# MCU.net
KiCad netlist of a schematic drawn in Altium Designer
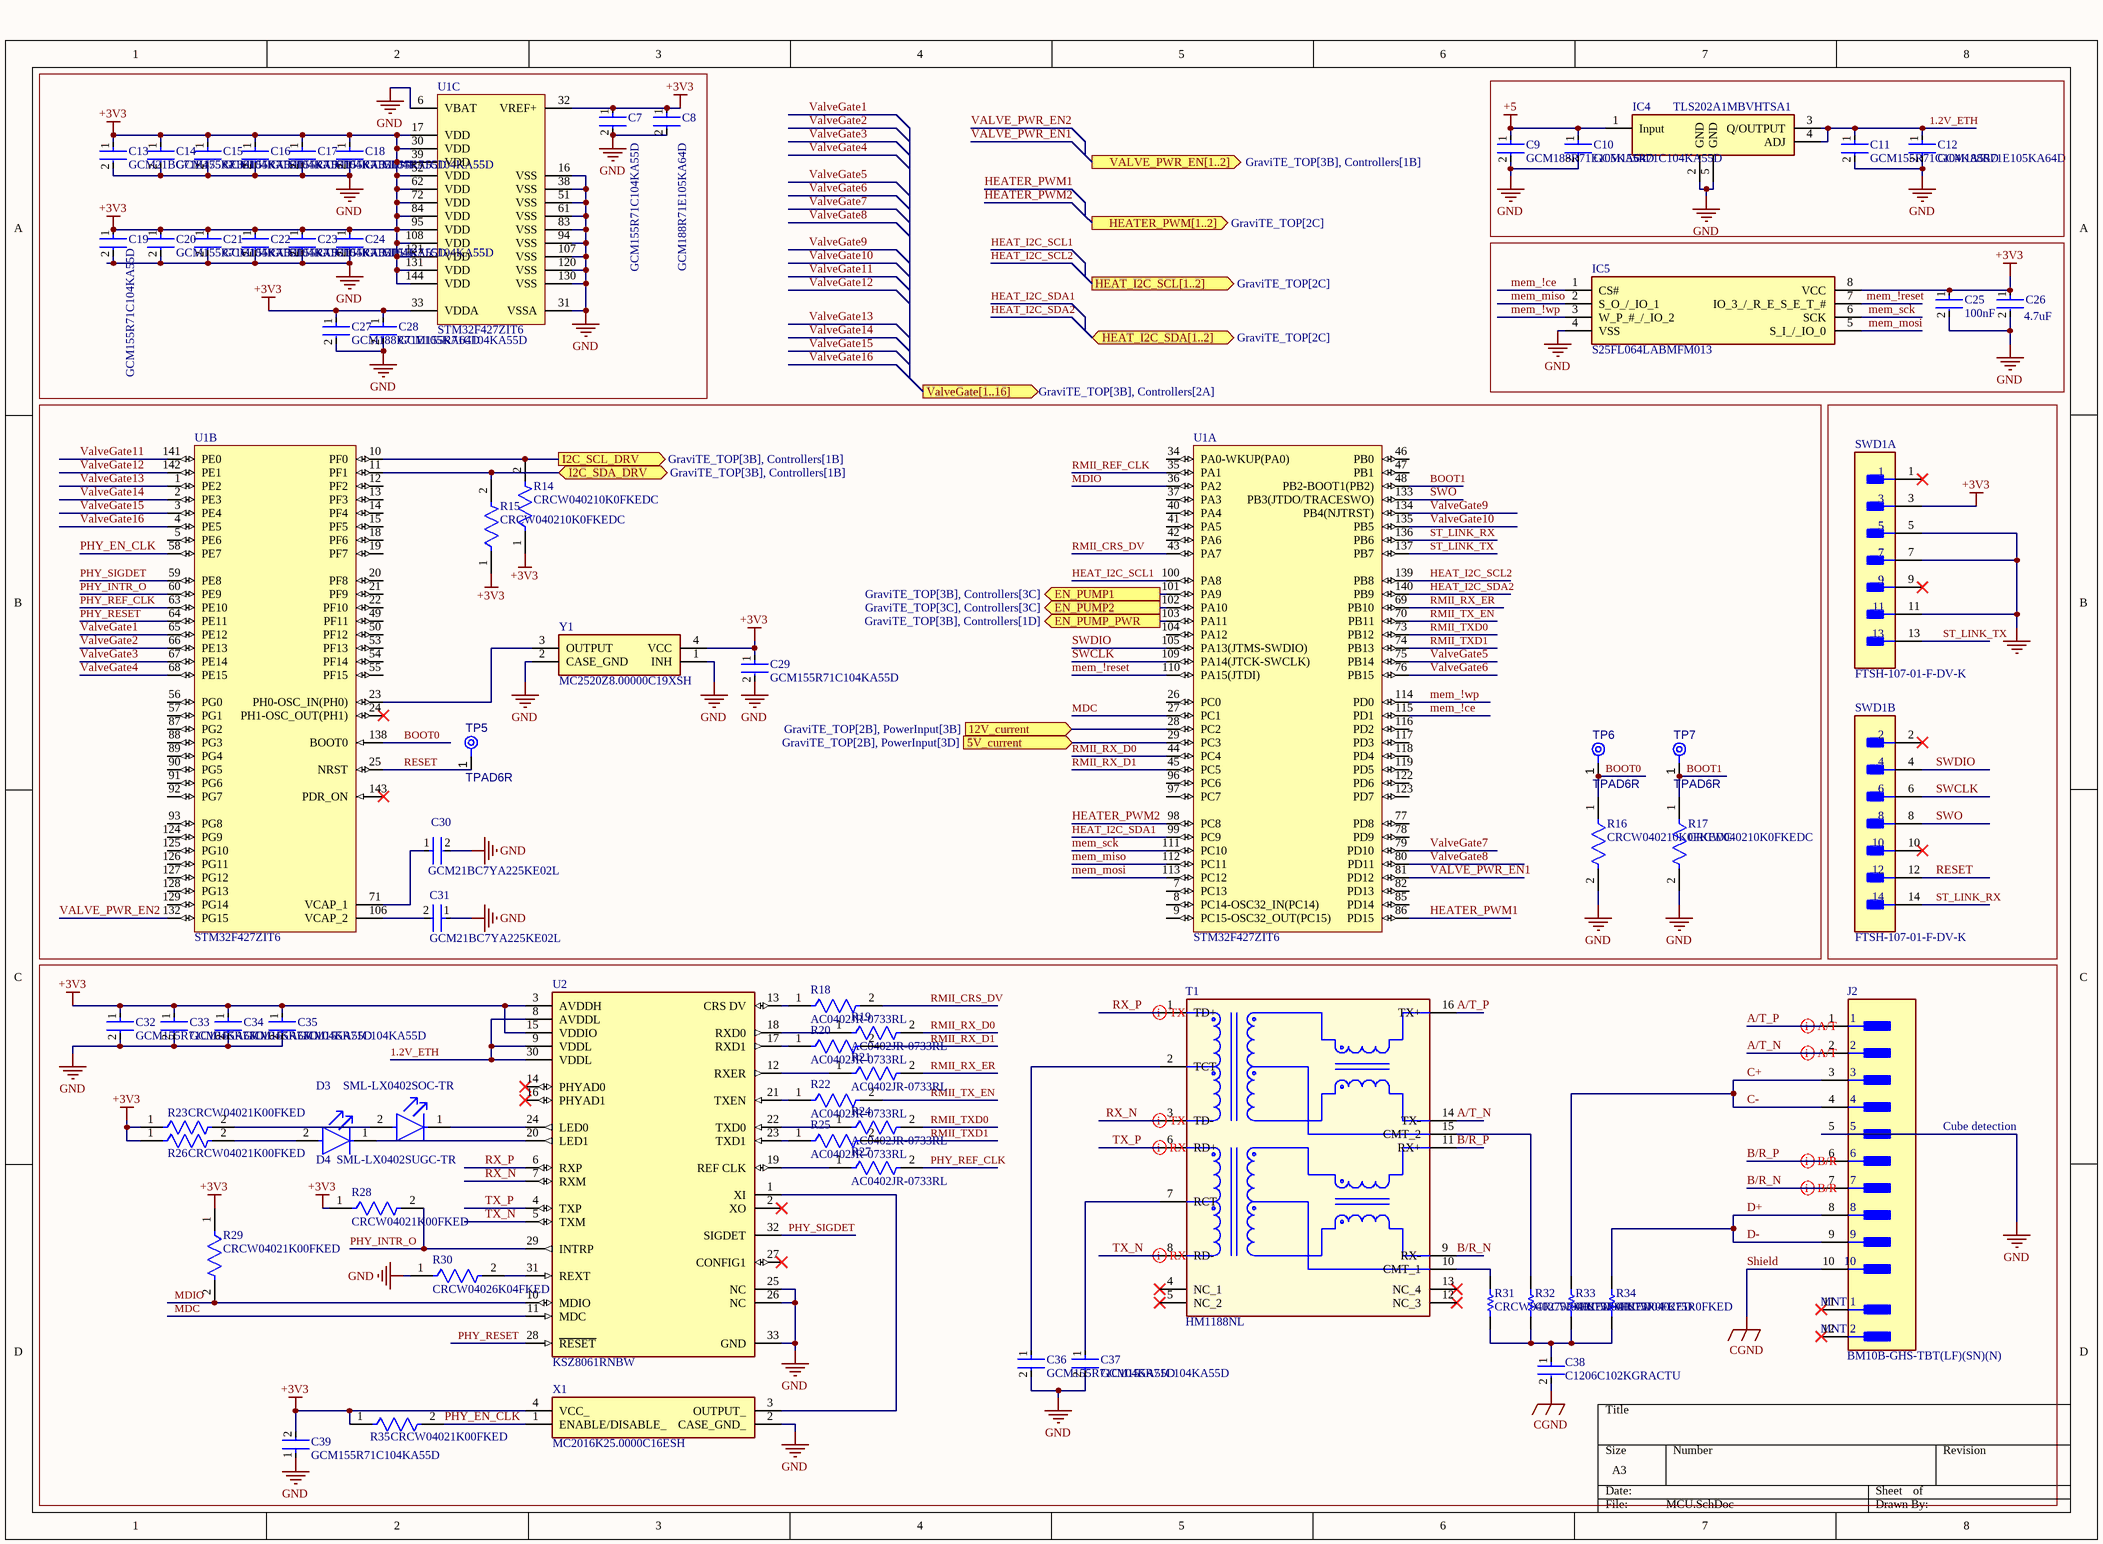
[diagram p0: MCU.SchDoc]

(export (version "E")
  (design (tool "Eeschema 10.0.6"))
  (components
    (comp (ref "C7")
      (value "GCM155R71C104KA55D")
      (footprint "FP-GCM155-0_05-IPC_C")
      (description "Ceramic Capacitor for Automotive 100nF ±10% 16VDC X7R 0402 Paper T/R")
      (fields (field (name "VOLTAGE") "16V") (field (name "TOLERANCE") "10%"))
      (libsource (lib "Altium Content Vault") (part "02cd4be3c70576c341d710602a673aa"))
    )
    (comp (ref "C8")
      (value "GCM188R71E105KA64D")
      (footprint "FP-GCM188-0_1-MFG")
      (fields (field (name "TOLERANCE") "10%") (field (name "VOLTAGE") "25V"))
      (libsource (lib "Altium Content Vault") (part "02cd4be3c70576c341d710602a673aa"))
    )
    (comp (ref "C9")
      (value "GCM188R71E105KA64D")
      (footprint "FP-GCM188-0_1-MFG")
      (fields (field (name "TOLERANCE") "10%") (field (name "VOLTAGE") "25V"))
      (libsource (lib "Altium Content Vault") (part "02cd4be3c70576c341d710602a673aa"))
    )
    (comp (ref "C10")
      (value "GCM155R71C104KA55D")
      (footprint "FP-GCM155-0_05-IPC_C")
      (description "Ceramic Capacitor for Automotive 100nF ±10% 16VDC X7R 0402 Paper T/R")
      (fields (field (name "VOLTAGE") "16V") (field (name "TOLERANCE") "10%"))
      (libsource (lib "Altium Content Vault") (part "02cd4be3c70576c341d710602a673aa"))
    )
    (comp (ref "C11")
      (value "GCM155R71C104KA55D")
      (footprint "FP-GCM155-0_05-IPC_C")
      (description "Ceramic Capacitor for Automotive 100nF ±10% 16VDC X7R 0402 Paper T/R")
      (fields (field (name "VOLTAGE") "16V") (field (name "TOLERANCE") "10%"))
      (libsource (lib "Altium Content Vault") (part "02cd4be3c70576c341d710602a673aa"))
    )
    (comp (ref "C12")
      (value "GCM188R71E105KA64D")
      (footprint "FP-GCM188-0_1-MFG")
      (fields (field (name "TOLERANCE") "10%") (field (name "VOLTAGE") "25V"))
      (libsource (lib "Altium Content Vault") (part "02cd4be3c70576c341d710602a673aa"))
    )
    (comp (ref "C13")
      (value "GCM21BC71E475KE36L")
      (footprint "FP-GCM21B-0_2-e0_2_0_7-IPC_C")
      (description "Ceramic Capacitor for Automotive 4.7uF ±10% 25VDC X7S 0805 Embossed T/R")
      (fields (field (name "TOLERANCE") "10%"))
      (libsource (lib "Altium Content Vault") (part "11868f565c42a9108669ba33697ecf6"))
    )
    (comp (ref "C14")
      (value "GCM155R71C104KA55D")
      (footprint "FP-GCM155-0_05-IPC_C")
      (description "Ceramic Capacitor for Automotive 100nF ±10% 16VDC X7R 0402 Paper T/R")
      (fields (field (name "VOLTAGE") "16V") (field (name "TOLERANCE") "10%"))
      (libsource (lib "Altium Content Vault") (part "02cd4be3c70576c341d710602a673aa"))
    )
    (comp (ref "C15")
      (value "GCM155R71C104KA55D")
      (footprint "FP-GCM155-0_05-IPC_C")
      (description "Ceramic Capacitor for Automotive 100nF ±10% 16VDC X7R 0402 Paper T/R")
      (fields (field (name "VOLTAGE") "16V") (field (name "TOLERANCE") "10%"))
      (libsource (lib "Altium Content Vault") (part "02cd4be3c70576c341d710602a673aa"))
    )
    (comp (ref "C16")
      (value "GCM155R71C104KA55D")
      (footprint "FP-GCM155-0_05-IPC_C")
      (description "Ceramic Capacitor for Automotive 100nF ±10% 16VDC X7R 0402 Paper T/R")
      (fields (field (name "VOLTAGE") "16V") (field (name "TOLERANCE") "10%"))
      (libsource (lib "Altium Content Vault") (part "02cd4be3c70576c341d710602a673aa"))
    )
    (comp (ref "C17")
      (value "GCM155R71C104KA55D")
      (footprint "FP-GCM155-0_05-IPC_C")
      (description "Ceramic Capacitor for Automotive 100nF ±10% 16VDC X7R 0402 Paper T/R")
      (fields (field (name "VOLTAGE") "16V") (field (name "TOLERANCE") "10%"))
      (libsource (lib "Altium Content Vault") (part "02cd4be3c70576c341d710602a673aa"))
    )
    (comp (ref "C18")
      (value "GCM155R71C104KA55D")
      (footprint "FP-GCM155-0_05-IPC_C")
      (description "Ceramic Capacitor for Automotive 100nF ±10% 16VDC X7R 0402 Paper T/R")
      (fields (field (name "VOLTAGE") "16V") (field (name "TOLERANCE") "10%"))
      (libsource (lib "Altium Content Vault") (part "02cd4be3c70576c341d710602a673aa"))
    )
    (comp (ref "C19")
      (value "GCM155R71C104KA55D")
      (footprint "FP-GCM155-0_05-IPC_C")
      (description "Ceramic Capacitor for Automotive 100nF ±10% 16VDC X7R 0402 Paper T/R")
      (fields (field (name "VOLTAGE") "16V") (field (name "TOLERANCE") "10%"))
      (libsource (lib "Altium Content Vault") (part "02cd4be3c70576c341d710602a673aa"))
    )
    (comp (ref "C20")
      (value "GCM155R71C104KA55D")
      (footprint "FP-GCM155-0_05-IPC_C")
      (description "Ceramic Capacitor for Automotive 100nF ±10% 16VDC X7R 0402 Paper T/R")
      (fields (field (name "VOLTAGE") "16V") (field (name "TOLERANCE") "10%"))
      (libsource (lib "Altium Content Vault") (part "02cd4be3c70576c341d710602a673aa"))
    )
    (comp (ref "C21")
      (value "GCM155R71C104KA55D")
      (footprint "FP-GCM155-0_05-IPC_C")
      (description "Ceramic Capacitor for Automotive 100nF ±10% 16VDC X7R 0402 Paper T/R")
      (fields (field (name "VOLTAGE") "16V") (field (name "TOLERANCE") "10%"))
      (libsource (lib "Altium Content Vault") (part "02cd4be3c70576c341d710602a673aa"))
    )
    (comp (ref "C22")
      (value "GCM155R71C104KA55D")
      (footprint "FP-GCM155-0_05-IPC_C")
      (description "Ceramic Capacitor for Automotive 100nF ±10% 16VDC X7R 0402 Paper T/R")
      (fields (field (name "VOLTAGE") "16V") (field (name "TOLERANCE") "10%"))
      (libsource (lib "Altium Content Vault") (part "02cd4be3c70576c341d710602a673aa"))
    )
    (comp (ref "C23")
      (value "GCM155R71C104KA55D")
      (footprint "FP-GCM155-0_05-IPC_C")
      (description "Ceramic Capacitor for Automotive 100nF ±10% 16VDC X7R 0402 Paper T/R")
      (fields (field (name "VOLTAGE") "16V") (field (name "TOLERANCE") "10%"))
      (libsource (lib "Altium Content Vault") (part "02cd4be3c70576c341d710602a673aa"))
    )
    (comp (ref "C24")
      (value "GCM155R71C104KA55D")
      (footprint "FP-GCM155-0_05-IPC_C")
      (description "Ceramic Capacitor for Automotive 100nF ±10% 16VDC X7R 0402 Paper T/R")
      (fields (field (name "VOLTAGE") "16V") (field (name "TOLERANCE") "10%"))
      (libsource (lib "Altium Content Vault") (part "02cd4be3c70576c341d710602a673aa"))
    )
    (comp (ref "C25")
      (value "100nF")
      (footprint "FP-GCM155-0_05-IPC_C")
      (description "Ceramic Capacitor for Automotive 100nF ±10% 16VDC X7R 0402 Paper T/R")
      (fields (field (name "VOLTAGE") "16V") (field (name "TOLERANCE") "10%"))
      (libsource (lib "Altium Content Vault") (part "02cd4be3c70576c341d710602a673aa"))
    )
    (comp (ref "C26")
      (value "4.7uF")
      (footprint "FP-GCM21B-0_2-e0_2_0_7-IPC_C")
      (description "Ceramic Capacitor for Automotive 4.7uF ±10% 25VDC X7S 0805 Embossed T/R")
      (fields (field (name "TOLERANCE") "10%"))
      (libsource (lib "Altium Content Vault") (part "11868f565c42a9108669ba33697ecf6"))
    )
    (comp (ref "C27")
      (value "GCM188R71E105KA64D")
      (footprint "FP-GCM188-0_1-MFG")
      (fields (field (name "TOLERANCE") "10%") (field (name "VOLTAGE") "25V"))
      (libsource (lib "Altium Content Vault") (part "02cd4be3c70576c341d710602a673aa"))
    )
    (comp (ref "C28")
      (value "GCM155R71C104KA55D")
      (footprint "FP-GCM155-0_05-IPC_C")
      (description "Ceramic Capacitor for Automotive 100nF ±10% 16VDC X7R 0402 Paper T/R")
      (fields (field (name "VOLTAGE") "16V") (field (name "TOLERANCE") "10%"))
      (libsource (lib "Altium Content Vault") (part "02cd4be3c70576c341d710602a673aa"))
    )
    (comp (ref "C29")
      (value "GCM155R71C104KA55D")
      (footprint "FP-GCM155-0_05-IPC_C")
      (description "Ceramic Capacitor for Automotive 100nF ±10% 16VDC X7R 0402 Paper T/R")
      (fields (field (name "VOLTAGE") "16V") (field (name "TOLERANCE") "10%"))
      (libsource (lib "Altium Content Vault") (part "02cd4be3c70576c341d710602a673aa"))
    )
    (comp (ref "C30")
      (value "GCM21BC7YA225KE02L")
      (footprint "FP-GCM21B-0_15-MFG")
      (description "Ceramic Capacitor for Automotive 2.2uF ±10% 35VDC X7S 0805 Embossed T/R")
      (fields (field (name "TOLERANCE") "10%"))
      (libsource (lib "Altium Content Vault") (part "02cd4be3c70576c341d710602a673aa"))
    )
    (comp (ref "C31")
      (value "GCM21BC7YA225KE02L")
      (footprint "FP-GCM21B-0_15-MFG")
      (description "Ceramic Capacitor for Automotive 2.2uF ±10% 35VDC X7S 0805 Embossed T/R")
      (fields (field (name "TOLERANCE") "10%"))
      (libsource (lib "Altium Content Vault") (part "02cd4be3c70576c341d710602a673aa"))
    )
    (comp (ref "C32")
      (value "GCM155R71C104KA55D")
      (footprint "FP-GCM155-0_05-IPC_C")
      (description "Ceramic Capacitor for Automotive 100nF ±10% 16VDC X7R 0402 Paper T/R")
      (fields (field (name "VOLTAGE") "16V") (field (name "TOLERANCE") "10%"))
      (libsource (lib "Altium Content Vault") (part "02cd4be3c70576c341d710602a673aa"))
    )
    (comp (ref "C33")
      (value "GCM155R71C104KA55D")
      (footprint "FP-GCM155-0_05-IPC_C")
      (description "Ceramic Capacitor for Automotive 100nF ±10% 16VDC X7R 0402 Paper T/R")
      (fields (field (name "VOLTAGE") "16V") (field (name "TOLERANCE") "10%"))
      (libsource (lib "Altium Content Vault") (part "02cd4be3c70576c341d710602a673aa"))
    )
    (comp (ref "C34")
      (value "GCM155R71C104KA55D")
      (footprint "FP-GCM155-0_05-IPC_C")
      (description "Ceramic Capacitor for Automotive 100nF ±10% 16VDC X7R 0402 Paper T/R")
      (fields (field (name "VOLTAGE") "16V") (field (name "TOLERANCE") "10%"))
      (libsource (lib "Altium Content Vault") (part "02cd4be3c70576c341d710602a673aa"))
    )
    (comp (ref "C35")
      (value "GCM155R71C104KA55D")
      (footprint "FP-GCM155-0_05-IPC_C")
      (description "Ceramic Capacitor for Automotive 100nF ±10% 16VDC X7R 0402 Paper T/R")
      (fields (field (name "VOLTAGE") "16V") (field (name "TOLERANCE") "10%"))
      (libsource (lib "Altium Content Vault") (part "02cd4be3c70576c341d710602a673aa"))
    )
    (comp (ref "C36")
      (value "GCM155R71C104KA55D")
      (footprint "FP-GCM155-0_05-IPC_C")
      (description "Ceramic Capacitor for Automotive 100nF ±10% 16VDC X7R 0402 Paper T/R")
      (fields (field (name "VOLTAGE") "16V") (field (name "TOLERANCE") "10%"))
      (libsource (lib "Altium Content Vault") (part "02cd4be3c70576c341d710602a673aa"))
    )
    (comp (ref "C37")
      (value "GCM155R71C104KA55D")
      (footprint "FP-GCM155-0_05-IPC_C")
      (description "Ceramic Capacitor for Automotive 100nF ±10% 16VDC X7R 0402 Paper T/R")
      (fields (field (name "VOLTAGE") "16V") (field (name "TOLERANCE") "10%"))
      (libsource (lib "Altium Content Vault") (part "02cd4be3c70576c341d710602a673aa"))
    )
    (comp (ref "C38")
      (value "C1206C102KGRACTU")
      (footprint "FP-C1206C-EF-MFG")
      (description "CAP CER 1000PF 2KV X7R 1206")
      (fields (field (name "VOLTAGE") "2kV") (field (name "TOLERANCE") "10%"))
      (libsource (lib "Altium Content Vault") (part "b4654b650e69147ec39a6b967a45e02"))
    )
    (comp (ref "C39")
      (value "GCM155R71C104KA55D")
      (footprint "FP-GCM155-0_05-IPC_C")
      (description "Ceramic Capacitor for Automotive 100nF ±10% 16VDC X7R 0402 Paper T/R")
      (fields (field (name "VOLTAGE") "16V") (field (name "TOLERANCE") "10%"))
      (libsource (lib "Altium Content Vault") (part "02cd4be3c70576c341d710602a673aa"))
    )
    (comp (ref "D3")
      (value "SML-LX0402SOC-TR")
      (footprint "FP-SML-LX0402SOC-TR-MFG")
      (description "LED ORANGE CLEAR SMD")
      (libsource (lib "Altium Content Vault") (part "8706943c75ba83719d021d2fdc84c58"))
    )
    (comp (ref "D4")
      (value "SML-LX0402SUGC-TR")
      (footprint "FP-SML-LX0402SUGC-TR-MFG")
      (description "LED GREEN CLEAR SMD")
      (libsource (lib "Altium Content Vault") (part "8706943c75ba83719d021d2fdc84c58"))
    )
    (comp (ref "IC4")
      (value "TLS202A1MBVHTSA1")
      (footprint "SamacSys:TLS202A1MBVHTSA1")
      (description "Integrated Circuit")
      (fields (field (name "MOUSER PART NUMBER") "726-TLS202A1MBVHTSA1"))
      (libsource (lib "SamacSys") (part "TLS202A1MBVHTSA1"))
    )
    (comp (ref "IC5")
      (value "S25FL064LABMFM013")
      (footprint "SamacSys:SOIC127P800X216-8N")
      (description "Integrated Circuit")
      (fields (field (name "MOUSER PART NUMBER") "727-S25FL064LAMFM013"))
      (libsource (lib "*") (part "S25FL064LABMFM013"))
    )
    (comp (ref "J2")
      (value "BM10B-GHS-TBT(LF)(SN)(N)")
      (footprint "FP-BM10B-GHS-TBT_LF_SN-MFG")
      (description "CONN HEADER SMD 10POS 1.25MM")
      (libsource (lib "Altium Content Vault") (part "75b8bc8596cc75ee3b2e8049366f7d6"))
    )
    (comp (ref "R14")
      (value "CRCW040210K0FKEDC")
      (footprint "FP-CRCW0402-C-e3-IPC_C")
      (description "RES 10K OHM 1% 1/16W 0402")
      (fields (field (name "TOLERANCE") "1%"))
      (libsource (lib "Altium Content Vault") (part "1029c3af85768c4190bb7ad29bc67b5"))
    )
    (comp (ref "R15")
      (value "CRCW040210K0FKEDC")
      (footprint "FP-CRCW0402-C-e3-IPC_C")
      (description "RES 10K OHM 1% 1/16W 0402")
      (fields (field (name "TOLERANCE") "1%"))
      (libsource (lib "Altium Content Vault") (part "1029c3af85768c4190bb7ad29bc67b5"))
    )
    (comp (ref "R16")
      (value "CRCW040210K0FKEDC")
      (footprint "FP-CRCW0402-C-e3-IPC_C")
      (description "RES 10K OHM 1% 1/16W 0402")
      (fields (field (name "TOLERANCE") "1%"))
      (libsource (lib "Altium Content Vault") (part "1029c3af85768c4190bb7ad29bc67b5"))
    )
    (comp (ref "R17")
      (value "CRCW040210K0FKEDC")
      (footprint "FP-CRCW0402-C-e3-IPC_C")
      (description "RES 10K OHM 1% 1/16W 0402")
      (fields (field (name "TOLERANCE") "1%"))
      (libsource (lib "Altium Content Vault") (part "1029c3af85768c4190bb7ad29bc67b5"))
    )
    (comp (ref "R18")
      (value "AC0402JR-0733RL")
      (footprint "FP-AC0402-IPC_B")
      (description "RES 33Ω ±5% 0.063W 0402")
      (fields (field (name "TOLERANCE") "5%"))
      (libsource (lib "Altium Content Vault") (part "1029c3af85768c4190bb7ad29bc67b5"))
    )
    (comp (ref "R19")
      (value "AC0402JR-0733RL")
      (footprint "FP-AC0402-IPC_B")
      (description "RES 33Ω ±5% 0.063W 0402")
      (fields (field (name "TOLERANCE") "5%"))
      (libsource (lib "Altium Content Vault") (part "1029c3af85768c4190bb7ad29bc67b5"))
    )
    (comp (ref "R20")
      (value "AC0402JR-0733RL")
      (footprint "FP-AC0402-IPC_B")
      (description "RES 33Ω ±5% 0.063W 0402")
      (fields (field (name "TOLERANCE") "5%"))
      (libsource (lib "Altium Content Vault") (part "1029c3af85768c4190bb7ad29bc67b5"))
    )
    (comp (ref "R21")
      (value "AC0402JR-0733RL")
      (footprint "FP-AC0402-IPC_B")
      (description "RES 33Ω ±5% 0.063W 0402")
      (fields (field (name "TOLERANCE") "5%"))
      (libsource (lib "Altium Content Vault") (part "1029c3af85768c4190bb7ad29bc67b5"))
    )
    (comp (ref "R22")
      (value "AC0402JR-0733RL")
      (footprint "FP-AC0402-IPC_B")
      (description "RES 33Ω ±5% 0.063W 0402")
      (fields (field (name "TOLERANCE") "5%"))
      (libsource (lib "Altium Content Vault") (part "1029c3af85768c4190bb7ad29bc67b5"))
    )
    (comp (ref "R23")
      (value "CRCW04021K00FKED")
      (footprint "FP-CRCW0402-e3-MFG")
      (description "RES Thick Film, 1kΩ, 1%, 0.063W, 100ppm/°C, 0402")
      (fields (field (name "TOLERANCE") "1%"))
      (libsource (lib "Altium Content Vault") (part "1029c3af85768c4190bb7ad29bc67b5"))
    )
    (comp (ref "R24")
      (value "AC0402JR-0733RL")
      (footprint "FP-AC0402-IPC_B")
      (description "RES 33Ω ±5% 0.063W 0402")
      (fields (field (name "TOLERANCE") "5%"))
      (libsource (lib "Altium Content Vault") (part "1029c3af85768c4190bb7ad29bc67b5"))
    )
    (comp (ref "R25")
      (value "AC0402JR-0733RL")
      (footprint "FP-AC0402-IPC_B")
      (description "RES 33Ω ±5% 0.063W 0402")
      (fields (field (name "TOLERANCE") "5%"))
      (libsource (lib "Altium Content Vault") (part "1029c3af85768c4190bb7ad29bc67b5"))
    )
    (comp (ref "R26")
      (value "CRCW04021K00FKED")
      (footprint "FP-CRCW0402-e3-MFG")
      (description "RES Thick Film, 1kΩ, 1%, 0.063W, 100ppm/°C, 0402")
      (fields (field (name "TOLERANCE") "1%"))
      (libsource (lib "Altium Content Vault") (part "1029c3af85768c4190bb7ad29bc67b5"))
    )
    (comp (ref "R27")
      (value "AC0402JR-0733RL")
      (footprint "FP-AC0402-IPC_B")
      (description "RES 33Ω ±5% 0.063W 0402")
      (fields (field (name "TOLERANCE") "5%"))
      (libsource (lib "Altium Content Vault") (part "1029c3af85768c4190bb7ad29bc67b5"))
    )
    (comp (ref "R28")
      (value "CRCW04021K00FKED")
      (footprint "FP-CRCW0402-e3-MFG")
      (description "RES Thick Film, 1kΩ, 1%, 0.063W, 100ppm/°C, 0402")
      (fields (field (name "TOLERANCE") "1%"))
      (libsource (lib "Altium Content Vault") (part "1029c3af85768c4190bb7ad29bc67b5"))
    )
    (comp (ref "R29")
      (value "CRCW04021K00FKED")
      (footprint "FP-CRCW0402-e3-MFG")
      (description "RES Thick Film, 1kΩ, 1%, 0.063W, 100ppm/°C, 0402")
      (fields (field (name "TOLERANCE") "1%"))
      (libsource (lib "Altium Content Vault") (part "1029c3af85768c4190bb7ad29bc67b5"))
    )
    (comp (ref "R30")
      (value "CRCW04026K04FKED")
      (footprint "FP-CRCW0402-e3-IPC_A")
      (description "RES Thick Film, 6.04kΩ, 1%, 0.063W, 100ppm/°C, 0402")
      (fields (field (name "TOLERANCE") "1%"))
      (libsource (lib "Altium Content Vault") (part "1029c3af85768c4190bb7ad29bc67b5"))
    )
    (comp (ref "R31")
      (value "CRCW040275R0FKED")
      (footprint "RESC1005X40X25NL05T05")
      (fields (field (name "MANUFACTURER") "Vishay Dale"))
      (libsource (lib "Altium Content Vault") (part "RES"))
    )
    (comp (ref "R32")
      (value "CRCW040275R0FKED")
      (footprint "RESC1005X40X25NL05T05")
      (fields (field (name "MANUFACTURER") "Vishay Dale"))
      (libsource (lib "Altium Content Vault") (part "RES"))
    )
    (comp (ref "R33")
      (value "CRCW040275R0FKED")
      (footprint "RESC1005X40X25NL05T05")
      (fields (field (name "MANUFACTURER") "Vishay Dale"))
      (libsource (lib "Altium Content Vault") (part "RES"))
    )
    (comp (ref "R34")
      (value "CRCW040275R0FKED")
      (footprint "RESC1005X40X25NL05T05")
      (fields (field (name "MANUFACTURER") "Vishay Dale"))
      (libsource (lib "Altium Content Vault") (part "RES"))
    )
    (comp (ref "R35")
      (value "CRCW04021K00FKED")
      (footprint "FP-CRCW0402-e3-MFG")
      (description "RES Thick Film, 1kΩ, 1%, 0.063W, 100ppm/°C, 0402")
      (fields (field (name "TOLERANCE") "1%"))
      (libsource (lib "Altium Content Vault") (part "1029c3af85768c4190bb7ad29bc67b5"))
    )
    (comp (ref "SWD1")
      (value "FTSH-107-01-F-DV-K")
      (footprint "FP-FTSH-107-01-F-DV-K-MFG")
      (description "CONN HEADER SMD 14POS 1.27MM")
      (libsource (lib "Altium Content Vault") (part "ab214579d66ef07f87fa9c6f4e4f9ab"))
    )
    (comp (ref "T1")
      (value "HM1188NL")
      (footprint "SamacSys:HM1188NL")
      (description "Transformer")
      (fields (field (name "MOUSER PART NUMBER") "673-HM1188NL"))
      (libsource (lib "SamacSys") (part "HM1188NL"))
    )
    (comp (ref "TP5")
      (value "TPAD6R")
      (footprint "TP06R")
      (description "0.6mm round")
      (libsource (lib "Piotr Słonka - priv") (part "CMP-001-0001-4"))
    )
    (comp (ref "TP6")
      (value "TPAD6R")
      (footprint "TP06R")
      (description "0.6mm round")
      (libsource (lib "Piotr Słonka - priv") (part "CMP-001-0001-4"))
    )
    (comp (ref "TP7")
      (value "TPAD6R")
      (footprint "TP06R")
      (description "0.6mm round")
      (libsource (lib "Piotr Słonka - priv") (part "CMP-001-0001-4"))
    )
    (comp (ref "U1")
      (value "STM32F427ZIT6")
      (footprint "STM-LQFP144_V")
      (fields (field (name "MANUFACTURER") "STMicroelectronics"))
      (libsource (lib "Altium Content Vault") (part "MC-ARM-STM32F427-SQ144"))
    )
    (comp (ref "U2")
      (value "KSZ8061RNBW")
      (footprint "FP-QFN55-32LD-PL-5-IPC_A")
      (description "IC TRANSCEIVER FULL 1/1 32QFN")
      (libsource (lib "Altium Content Vault") (part "ab1a5c9758dd1d3a4c2434b36c3754f"))
    )
    (comp (ref "X1")
      (value "MC2016K25.0000C16ESH")
      (footprint "MC2016K250000C16ESH")
      (description "XTAL OSC XO 25.0000MHZ CMOS SMD")
      (fields (field (name "MOUSER PART NUMBER") "581-MC2016K25.C16ESH"))
      (libsource (lib "MC2016K25.0000C16ESH") (part "MC2016K25.0000C16ESH"))
    )
    (comp (ref "Y1")
      (value "MC2520Z8.00000C19XSH")
      (footprint "SamacSys:MC2520Z800000C19XSH")
      (description "Crystal or Oscillator")
      (fields (field (name "MOUSER PART NUMBER") "346-MC2520Z8.00000C1"))
      (libsource (lib "SamacSys") (part "MC2520Z8.00000C19XSH"))
    )
  )
  (nets
    (net (code "1") (name "+3V3") (class "Default")
      (node (ref "C13") (pin "1") (pinfunction "1_1") (pintype "passive"))
      (node (ref "C14") (pin "1") (pinfunction "1_1") (pintype "passive"))
      (node (ref "C15") (pin "1") (pinfunction "1_1") (pintype "passive"))
      (node (ref "C16") (pin "1") (pinfunction "1_1") (pintype "passive"))
      (node (ref "C17") (pin "1") (pinfunction "1_1") (pintype "passive"))
      (node (ref "C18") (pin "1") (pinfunction "1_1") (pintype "passive"))
      (node (ref "C19") (pin "1") (pinfunction "1_1") (pintype "passive"))
      (node (ref "C20") (pin "1") (pinfunction "1_1") (pintype "passive"))
      (node (ref "C21") (pin "1") (pinfunction "1_1") (pintype "passive"))
      (node (ref "C22") (pin "1") (pinfunction "1_1") (pintype "passive"))
      (node (ref "C23") (pin "1") (pinfunction "1_1") (pintype "passive"))
      (node (ref "C24") (pin "1") (pinfunction "1_1") (pintype "passive"))
      (node (ref "C25") (pin "1") (pinfunction "1_1") (pintype "passive"))
      (node (ref "C26") (pin "1") (pinfunction "1_1") (pintype "passive"))
      (node (ref "C27") (pin "1") (pinfunction "1_1") (pintype "passive"))
      (node (ref "C28") (pin "1") (pinfunction "1_1") (pintype "passive"))
      (node (ref "C29") (pin "1") (pinfunction "1_1") (pintype "passive"))
      (node (ref "C32") (pin "1") (pinfunction "1_1") (pintype "passive"))
      (node (ref "C33") (pin "1") (pinfunction "1_1") (pintype "passive"))
      (node (ref "C34") (pin "1") (pinfunction "1_1") (pintype "passive"))
      (node (ref "C35") (pin "1") (pinfunction "1_1") (pintype "passive"))
      (node (ref "C39") (pin "2") (pinfunction "2_2") (pintype "passive"))
      (node (ref "C7") (pin "1") (pinfunction "1_1") (pintype "passive"))
      (node (ref "C8") (pin "1") (pinfunction "1_1") (pintype "passive"))
      (node (ref "IC5") (pin "8") (pinfunction "VCC_8") (pintype "passive"))
      (node (ref "R14") (pin "1") (pinfunction "1_1") (pintype "passive"))
      (node (ref "R15") (pin "1") (pinfunction "1_1") (pintype "passive"))
      (node (ref "R23") (pin "1") (pinfunction "1_1") (pintype "passive"))
      (node (ref "R26") (pin "1") (pinfunction "1_1") (pintype "passive"))
      (node (ref "R28") (pin "1") (pinfunction "1_1") (pintype "passive"))
      (node (ref "R29") (pin "1") (pinfunction "1_1") (pintype "passive"))
      (node (ref "R35") (pin "1") (pinfunction "1_1") (pintype "passive"))
      (node (ref "SWD1") (pin "3") (pinfunction "3_3") (pintype "passive"))
      (node (ref "U1") (pin "108") (pinfunction "VDD_108") (pintype "power_in"))
      (node (ref "U1") (pin "121") (pinfunction "VDD_121") (pintype "power_in"))
      (node (ref "U1") (pin "131") (pinfunction "VDD_131") (pintype "power_in"))
      (node (ref "U1") (pin "144") (pinfunction "VDD_144") (pintype "power_in"))
      (node (ref "U1") (pin "17") (pinfunction "VDD_17") (pintype "power_in"))
      (node (ref "U1") (pin "30") (pinfunction "VDD_30") (pintype "power_in"))
      (node (ref "U1") (pin "32") (pinfunction "VREF+_32") (pintype "power_in"))
      (node (ref "U1") (pin "33") (pinfunction "VDDA_33") (pintype "power_in"))
      (node (ref "U1") (pin "39") (pinfunction "VDD_39") (pintype "power_in"))
      (node (ref "U1") (pin "52") (pinfunction "VDD_52") (pintype "power_in"))
      (node (ref "U1") (pin "62") (pinfunction "VDD_62") (pintype "power_in"))
      (node (ref "U1") (pin "72") (pinfunction "VDD_72") (pintype "power_in"))
      (node (ref "U1") (pin "84") (pinfunction "VDD_84") (pintype "power_in"))
      (node (ref "U1") (pin "95") (pinfunction "VDD_95") (pintype "power_in"))
      (node (ref "U2") (pin "15") (pinfunction "VDDIO_15") (pintype "power_in"))
      (node (ref "U2") (pin "3") (pinfunction "AVDDH_3") (pintype "power_in"))
      (node (ref "X1") (pin "4") (pinfunction "VCC__4") (pintype "passive"))
      (node (ref "Y1") (pin "4") (pinfunction "VCC_4") (pintype "passive"))
    )
    (net (code "2") (name "+5") (class "Default")
      (node (ref "C10") (pin "1") (pinfunction "1_1") (pintype "passive"))
      (node (ref "C9") (pin "1") (pinfunction "1_1") (pintype "passive"))
      (node (ref "IC4") (pin "1") (pinfunction "Input_1") (pintype "passive"))
    )
    (net (code "3") (name "/1.2V_ETH") (class "Default")
      (node (ref "C11") (pin "1") (pinfunction "1_1") (pintype "passive"))
      (node (ref "C12") (pin "1") (pinfunction "1_1") (pintype "passive"))
      (node (ref "IC4") (pin "3") (pinfunction "Q/OUTPUT_3") (pintype "passive"))
      (node (ref "IC4") (pin "4") (pinfunction "ADJ_4") (pintype "passive"))
      (node (ref "U2") (pin "30") (pinfunction "VDDL_30") (pintype "power_in"))
      (node (ref "U2") (pin "8") (pinfunction "AVDDL_8") (pintype "power_in"))
      (node (ref "U2") (pin "9") (pinfunction "VDDL_9") (pintype "power_in"))
    )
    (net (code "4") (name "/5V_current") (class "Default")
      (node (ref "U1") (pin "29") (pinfunction "PC3_29") (pintype "bidirectional"))
    )
    (net (code "5") (name "/12V_current") (class "Default")
      (node (ref "U1") (pin "28") (pinfunction "PC2_28") (pintype "bidirectional"))
    )
    (net (code "6") (name "/A{slash}T_N") (class "Default")
      (node (ref "J2") (pin "2") (pinfunction "2_2") (pintype "passive"))
      (node (ref "T1") (pin "14") (pinfunction "TX-_14") (pintype "passive"))
    )
    (net (code "7") (name "/A{slash}T_P") (class "Default")
      (node (ref "J2") (pin "1") (pinfunction "1_1") (pintype "passive"))
      (node (ref "T1") (pin "16") (pinfunction "TX+_16") (pintype "passive"))
    )
    (net (code "8") (name "/BOOT0") (class "Default")
      (node (ref "R16") (pin "1") (pinfunction "1_1") (pintype "passive"))
      (node (ref "TP6") (pin "1") (pinfunction "TP_1") (pintype "passive"))
      (node (ref "U1") (pin "138") (pinfunction "BOOT0_138") (pintype "input"))
    )
    (net (code "9") (name "/BOOT1") (class "Default")
      (node (ref "R17") (pin "1") (pinfunction "1_1") (pintype "passive"))
      (node (ref "TP7") (pin "1") (pinfunction "TP_1") (pintype "passive"))
      (node (ref "U1") (pin "48") (pinfunction "PB2-BOOT1(PB2)_48") (pintype "bidirectional"))
    )
    (net (code "10") (name "/B{slash}R_N") (class "Default")
      (node (ref "J2") (pin "7") (pinfunction "7_7") (pintype "passive"))
      (node (ref "T1") (pin "9") (pinfunction "RX-_9") (pintype "passive"))
    )
    (net (code "11") (name "/B{slash}R_P") (class "Default")
      (node (ref "J2") (pin "6") (pinfunction "6_6") (pintype "passive"))
      (node (ref "T1") (pin "11") (pinfunction "RX+_11") (pintype "passive"))
    )
    (net (code "12") (name "/C+") (class "Default")
      (node (ref "J2") (pin "3") (pinfunction "3_3") (pintype "passive"))
      (node (ref "J2") (pin "4") (pinfunction "4_4") (pintype "passive"))
      (node (ref "R33") (pin "2") (pinfunction "2_2") (pintype "passive"))
    )
    (net (code "13") (name "/D+") (class "Default")
      (node (ref "J2") (pin "8") (pinfunction "8_8") (pintype "passive"))
      (node (ref "J2") (pin "9") (pinfunction "9_9") (pintype "passive"))
      (node (ref "R34") (pin "2") (pinfunction "2_2") (pintype "passive"))
    )
    (net (code "14") (name "/EN_PUMP1") (class "Default")
      (node (ref "U1") (pin "101") (pinfunction "PA9_101") (pintype "bidirectional"))
    )
    (net (code "15") (name "/EN_PUMP2") (class "Default")
      (node (ref "U1") (pin "102") (pinfunction "PA10_102") (pintype "bidirectional"))
    )
    (net (code "16") (name "/EN_PUMP_PWR") (class "Default")
      (node (ref "U1") (pin "103") (pinfunction "PA11_103") (pintype "bidirectional"))
    )
    (net (code "17") (name "/HEATER_PWM1") (class "Default")
      (node (ref "U1") (pin "86") (pinfunction "PD15_86") (pintype "bidirectional"))
    )
    (net (code "18") (name "/HEATER_PWM2") (class "Default")
      (node (ref "U1") (pin "98") (pinfunction "PC8_98") (pintype "bidirectional"))
    )
    (net (code "20") (name "/HEAT_I2C_SCL1") (class "Default")
      (node (ref "U1") (pin "100") (pinfunction "PA8_100") (pintype "bidirectional"))
    )
    (net (code "21") (name "/HEAT_I2C_SCL2") (class "Default")
      (node (ref "U1") (pin "139") (pinfunction "PB8_139") (pintype "bidirectional"))
    )
    (net (code "23") (name "/HEAT_I2C_SDA1") (class "Default")
      (node (ref "U1") (pin "99") (pinfunction "PC9_99") (pintype "bidirectional"))
    )
    (net (code "24") (name "/HEAT_I2C_SDA2") (class "Default")
      (node (ref "U1") (pin "140") (pinfunction "PB9_140") (pintype "bidirectional"))
    )
    (net (code "26") (name "/I2C_SCL_DRV") (class "Default")
      (node (ref "R14") (pin "2") (pinfunction "2_2") (pintype "passive"))
      (node (ref "U1") (pin "10") (pinfunction "PF0_10") (pintype "bidirectional"))
    )
    (net (code "27") (name "/I2C_SDA_DRV") (class "Default")
      (node (ref "R15") (pin "2") (pinfunction "2_2") (pintype "passive"))
      (node (ref "U1") (pin "11") (pinfunction "PF1_11") (pintype "bidirectional"))
    )
    (net (code "28") (name "/MDC") (class "Default")
      (node (ref "U1") (pin "27") (pinfunction "PC1_27") (pintype "bidirectional"))
      (node (ref "U2") (pin "11") (pinfunction "MDC_11") (pintype "input"))
    )
    (net (code "29") (name "/MDIO") (class "Default")
      (node (ref "R29") (pin "2") (pinfunction "2_2") (pintype "passive"))
      (node (ref "U1") (pin "36") (pinfunction "PA2_36") (pintype "bidirectional"))
      (node (ref "U2") (pin "10") (pinfunction "MDIO_10") (pintype "bidirectional"))
    )
    (net (code "30") (name "/PHY_EN_CLK") (class "Default")
      (node (ref "R35") (pin "2") (pinfunction "2_2") (pintype "passive"))
      (node (ref "U1") (pin "58") (pinfunction "PE7_58") (pintype "bidirectional"))
      (node (ref "X1") (pin "1") (pinfunction "ENABLE/DISABLE__1") (pintype "passive"))
    )
    (net (code "31") (name "/PHY_INTR_O") (class "Default")
      (node (ref "R28") (pin "2") (pinfunction "2_2") (pintype "passive"))
      (node (ref "U1") (pin "60") (pinfunction "PE9_60") (pintype "bidirectional"))
      (node (ref "U2") (pin "29") (pinfunction "INTRP_29") (pintype "output"))
    )
    (net (code "32") (name "/PHY_REF_CLK") (class "Default")
      (node (ref "R27") (pin "2") (pinfunction "2_2") (pintype "passive"))
      (node (ref "U1") (pin "63") (pinfunction "PE10_63") (pintype "bidirectional"))
    )
    (net (code "33") (name "/PHY_RESET") (class "Default")
      (node (ref "U1") (pin "64") (pinfunction "PE11_64") (pintype "bidirectional"))
      (node (ref "U2") (pin "28") (pinfunction "~{RESET}_28") (pintype "input"))
    )
    (net (code "34") (name "/PHY_SIGDET") (class "Default")
      (node (ref "U1") (pin "59") (pinfunction "PE8_59") (pintype "bidirectional"))
      (node (ref "U2") (pin "32") (pinfunction "SIGDET_32") (pintype "passive"))
    )
    (net (code "35") (name "/RESET") (class "Default")
      (node (ref "SWD1") (pin "12") (pinfunction "12_12") (pintype "passive"))
      (node (ref "TP5") (pin "1") (pinfunction "TP_1") (pintype "passive"))
      (node (ref "U1") (pin "25") (pinfunction "NRST_25") (pintype "bidirectional"))
    )
    (net (code "36") (name "/RMII_CRS_DV") (class "Default")
      (node (ref "R18") (pin "2") (pinfunction "2_2") (pintype "passive"))
      (node (ref "U1") (pin "43") (pinfunction "PA7_43") (pintype "bidirectional"))
    )
    (net (code "37") (name "/RMII_REF_CLK") (class "Default")
      (node (ref "U1") (pin "35") (pinfunction "PA1_35") (pintype "bidirectional"))
    )
    (net (code "38") (name "/RMII_RX_D0") (class "Default")
      (node (ref "R19") (pin "2") (pinfunction "2_2") (pintype "passive"))
      (node (ref "U1") (pin "44") (pinfunction "PC4_44") (pintype "bidirectional"))
    )
    (net (code "39") (name "/RMII_RX_D1") (class "Default")
      (node (ref "R20") (pin "2") (pinfunction "2_2") (pintype "passive"))
      (node (ref "U1") (pin "45") (pinfunction "PC5_45") (pintype "bidirectional"))
    )
    (net (code "40") (name "/RMII_RX_ER") (class "Default")
      (node (ref "R21") (pin "2") (pinfunction "2_2") (pintype "passive"))
      (node (ref "U1") (pin "69") (pinfunction "PB10_69") (pintype "bidirectional"))
    )
    (net (code "41") (name "/RMII_TXD0") (class "Default")
      (node (ref "R24") (pin "2") (pinfunction "2_2") (pintype "passive"))
      (node (ref "U1") (pin "73") (pinfunction "PB12_73") (pintype "bidirectional"))
    )
    (net (code "42") (name "/RMII_TXD1") (class "Default")
      (node (ref "R25") (pin "2") (pinfunction "2_2") (pintype "passive"))
      (node (ref "U1") (pin "74") (pinfunction "PB13_74") (pintype "bidirectional"))
    )
    (net (code "43") (name "/RMII_TX_EN") (class "Default")
      (node (ref "R22") (pin "2") (pinfunction "2_2") (pintype "passive"))
      (node (ref "U1") (pin "70") (pinfunction "PB11_70") (pintype "bidirectional"))
    )
    (net (code "44") (name "/RX_N") (class "Default")
      (node (ref "T1") (pin "3") (pinfunction "TD-_3") (pintype "passive"))
      (node (ref "U2") (pin "7") (pinfunction "RXM_7") (pintype "bidirectional"))
    )
    (net (code "45") (name "/RX_P") (class "Default")
      (node (ref "T1") (pin "1") (pinfunction "TD+_1") (pintype "passive"))
      (node (ref "U2") (pin "6") (pinfunction "RXP_6") (pintype "bidirectional"))
    )
    (net (code "46") (name "/ST_LINK_RX") (class "Default")
      (node (ref "SWD1") (pin "14") (pinfunction "14_14") (pintype "passive"))
      (node (ref "U1") (pin "136") (pinfunction "PB6_136") (pintype "bidirectional"))
    )
    (net (code "47") (name "/ST_LINK_TX") (class "Default")
      (node (ref "SWD1") (pin "13") (pinfunction "13_13") (pintype "passive"))
      (node (ref "U1") (pin "137") (pinfunction "PB7_137") (pintype "bidirectional"))
    )
    (net (code "48") (name "/SWCLK") (class "Default")
      (node (ref "SWD1") (pin "6") (pinfunction "6_6") (pintype "passive"))
      (node (ref "U1") (pin "109") (pinfunction "PA14(JTCK-SWCLK)_109") (pintype "bidirectional"))
    )
    (net (code "49") (name "/SWDIO") (class "Default")
      (node (ref "SWD1") (pin "4") (pinfunction "4_4") (pintype "passive"))
      (node (ref "U1") (pin "105") (pinfunction "PA13(JTMS-SWDIO)_105") (pintype "bidirectional"))
    )
    (net (code "50") (name "/SWO") (class "Default")
      (node (ref "SWD1") (pin "8") (pinfunction "8_8") (pintype "passive"))
      (node (ref "U1") (pin "133") (pinfunction "PB3(JTDO/TRACESWO)_133") (pintype "bidirectional"))
    )
    (net (code "51") (name "/TX_N") (class "Default")
      (node (ref "T1") (pin "8") (pinfunction "RD-_8") (pintype "passive"))
      (node (ref "U2") (pin "5") (pinfunction "TXM_5") (pintype "bidirectional"))
    )
    (net (code "52") (name "/TX_P") (class "Default")
      (node (ref "T1") (pin "6") (pinfunction "RD+_6") (pintype "passive"))
      (node (ref "U2") (pin "4") (pinfunction "TXP_4") (pintype "bidirectional"))
    )
    (net (code "53") (name "/VALVE_PWR_EN1") (class "Default")
      (node (ref "U1") (pin "81") (pinfunction "PD12_81") (pintype "bidirectional"))
    )
    (net (code "54") (name "/VALVE_PWR_EN2") (class "Default")
      (node (ref "U1") (pin "132") (pinfunction "PG15_132") (pintype "bidirectional"))
    )
    (net (code "56") (name "/ValveGate1") (class "Default")
      (node (ref "U1") (pin "65") (pinfunction "PE12_65") (pintype "bidirectional"))
    )
    (net (code "57") (name "/ValveGate2") (class "Default")
      (node (ref "U1") (pin "66") (pinfunction "PE13_66") (pintype "bidirectional"))
    )
    (net (code "58") (name "/ValveGate3") (class "Default")
      (node (ref "U1") (pin "67") (pinfunction "PE14_67") (pintype "bidirectional"))
    )
    (net (code "59") (name "/ValveGate4") (class "Default")
      (node (ref "U1") (pin "68") (pinfunction "PE15_68") (pintype "bidirectional"))
    )
    (net (code "60") (name "/ValveGate5") (class "Default")
      (node (ref "U1") (pin "75") (pinfunction "PB14_75") (pintype "bidirectional"))
    )
    (net (code "61") (name "/ValveGate6") (class "Default")
      (node (ref "U1") (pin "76") (pinfunction "PB15_76") (pintype "bidirectional"))
    )
    (net (code "62") (name "/ValveGate7") (class "Default")
      (node (ref "U1") (pin "79") (pinfunction "PD10_79") (pintype "bidirectional"))
    )
    (net (code "63") (name "/ValveGate8") (class "Default")
      (node (ref "U1") (pin "80") (pinfunction "PD11_80") (pintype "bidirectional"))
    )
    (net (code "64") (name "/ValveGate9") (class "Default")
      (node (ref "U1") (pin "134") (pinfunction "PB4(NJTRST)_134") (pintype "bidirectional"))
    )
    (net (code "65") (name "/ValveGate10") (class "Default")
      (node (ref "U1") (pin "135") (pinfunction "PB5_135") (pintype "bidirectional"))
    )
    (net (code "66") (name "/ValveGate11") (class "Default")
      (node (ref "U1") (pin "141") (pinfunction "PE0_141") (pintype "bidirectional"))
    )
    (net (code "67") (name "/ValveGate12") (class "Default")
      (node (ref "U1") (pin "142") (pinfunction "PE1_142") (pintype "bidirectional"))
    )
    (net (code "68") (name "/ValveGate13") (class "Default")
      (node (ref "U1") (pin "1") (pinfunction "PE2_1") (pintype "bidirectional"))
    )
    (net (code "69") (name "/ValveGate14") (class "Default")
      (node (ref "U1") (pin "2") (pinfunction "PE3_2") (pintype "bidirectional"))
    )
    (net (code "70") (name "/ValveGate15") (class "Default")
      (node (ref "U1") (pin "3") (pinfunction "PE4_3") (pintype "bidirectional"))
    )
    (net (code "71") (name "/ValveGate16") (class "Default")
      (node (ref "U1") (pin "4") (pinfunction "PE5_4") (pintype "bidirectional"))
    )
    (net (code "73") (name "/mem_!ce") (class "Default")
      (node (ref "IC5") (pin "1") (pinfunction "CS#_1") (pintype "passive"))
      (node (ref "U1") (pin "115") (pinfunction "PD1_115") (pintype "bidirectional"))
    )
    (net (code "74") (name "/mem_!reset") (class "Default")
      (node (ref "IC5") (pin "7") (pinfunction "IO_3_/_R_E_S_E_T_#_7") (pintype "passive"))
      (node (ref "U1") (pin "110") (pinfunction "PA15(JTDI)_110") (pintype "bidirectional"))
    )
    (net (code "75") (name "/mem_!wp") (class "Default")
      (node (ref "IC5") (pin "3") (pinfunction "W_P_#_/_IO_2_3") (pintype "passive"))
      (node (ref "U1") (pin "114") (pinfunction "PD0_114") (pintype "bidirectional"))
    )
    (net (code "76") (name "/mem_miso") (class "Default")
      (node (ref "IC5") (pin "2") (pinfunction "S_O_/_IO_1_2") (pintype "passive"))
      (node (ref "U1") (pin "112") (pinfunction "PC11_112") (pintype "bidirectional"))
    )
    (net (code "77") (name "/mem_mosi") (class "Default")
      (node (ref "IC5") (pin "5") (pinfunction "S_I_/_IO_0_5") (pintype "passive"))
      (node (ref "U1") (pin "113") (pinfunction "PC12_113") (pintype "bidirectional"))
    )
    (net (code "78") (name "/mem_sck") (class "Default")
      (node (ref "IC5") (pin "6") (pinfunction "SCK_6") (pintype "passive"))
      (node (ref "U1") (pin "111") (pinfunction "PC10_111") (pintype "bidirectional"))
    )
    (net (code "79") (name "CGND") (class "Default")
      (node (ref "C38") (pin "2") (pinfunction "2_2") (pintype "passive"))
      (node (ref "J2") (pin "10") (pinfunction "10_10") (pintype "passive"))
    )
    (net (code "80") (name "GND") (class "Default")
      (node (ref "C10") (pin "2") (pinfunction "2_2") (pintype "passive"))
      (node (ref "C11") (pin "2") (pinfunction "2_2") (pintype "passive"))
      (node (ref "C12") (pin "2") (pinfunction "2_2") (pintype "passive"))
      (node (ref "C13") (pin "2") (pinfunction "2_2") (pintype "passive"))
      (node (ref "C14") (pin "2") (pinfunction "2_2") (pintype "passive"))
      (node (ref "C15") (pin "2") (pinfunction "2_2") (pintype "passive"))
      (node (ref "C16") (pin "2") (pinfunction "2_2") (pintype "passive"))
      (node (ref "C17") (pin "2") (pinfunction "2_2") (pintype "passive"))
      (node (ref "C18") (pin "2") (pinfunction "2_2") (pintype "passive"))
      (node (ref "C19") (pin "2") (pinfunction "2_2") (pintype "passive"))
      (node (ref "C20") (pin "2") (pinfunction "2_2") (pintype "passive"))
      (node (ref "C21") (pin "2") (pinfunction "2_2") (pintype "passive"))
      (node (ref "C22") (pin "2") (pinfunction "2_2") (pintype "passive"))
      (node (ref "C23") (pin "2") (pinfunction "2_2") (pintype "passive"))
      (node (ref "C24") (pin "2") (pinfunction "2_2") (pintype "passive"))
      (node (ref "C25") (pin "2") (pinfunction "2_2") (pintype "passive"))
      (node (ref "C26") (pin "2") (pinfunction "2_2") (pintype "passive"))
      (node (ref "C27") (pin "2") (pinfunction "2_2") (pintype "passive"))
      (node (ref "C28") (pin "2") (pinfunction "2_2") (pintype "passive"))
      (node (ref "C29") (pin "2") (pinfunction "2_2") (pintype "passive"))
      (node (ref "C30") (pin "2") (pinfunction "2_2") (pintype "passive"))
      (node (ref "C31") (pin "1") (pinfunction "1_1") (pintype "passive"))
      (node (ref "C32") (pin "2") (pinfunction "2_2") (pintype "passive"))
      (node (ref "C33") (pin "2") (pinfunction "2_2") (pintype "passive"))
      (node (ref "C34") (pin "2") (pinfunction "2_2") (pintype "passive"))
      (node (ref "C35") (pin "2") (pinfunction "2_2") (pintype "passive"))
      (node (ref "C36") (pin "2") (pinfunction "2_2") (pintype "passive"))
      (node (ref "C37") (pin "2") (pinfunction "2_2") (pintype "passive"))
      (node (ref "C39") (pin "1") (pinfunction "1_1") (pintype "passive"))
      (node (ref "C7") (pin "2") (pinfunction "2_2") (pintype "passive"))
      (node (ref "C8") (pin "2") (pinfunction "2_2") (pintype "passive"))
      (node (ref "C9") (pin "2") (pinfunction "2_2") (pintype "passive"))
      (node (ref "IC4") (pin "2") (pinfunction "GND_2") (pintype "passive"))
      (node (ref "IC4") (pin "5") (pinfunction "GND_5") (pintype "passive"))
      (node (ref "IC5") (pin "4") (pinfunction "VSS_4") (pintype "passive"))
      (node (ref "J2") (pin "5") (pinfunction "5_5") (pintype "passive"))
      (node (ref "R16") (pin "2") (pinfunction "2_2") (pintype "passive"))
      (node (ref "R17") (pin "2") (pinfunction "2_2") (pintype "passive"))
      (node (ref "R30") (pin "1") (pinfunction "1_1") (pintype "passive"))
      (node (ref "SWD1") (pin "11") (pinfunction "11_11") (pintype "passive"))
      (node (ref "SWD1") (pin "5") (pinfunction "5_5") (pintype "passive"))
      (node (ref "SWD1") (pin "7") (pinfunction "7_7") (pintype "passive"))
      (node (ref "U1") (pin "107") (pinfunction "VSS_107") (pintype "power_in"))
      (node (ref "U1") (pin "120") (pinfunction "VSS_120") (pintype "power_in"))
      (node (ref "U1") (pin "130") (pinfunction "VSS_130") (pintype "power_in"))
      (node (ref "U1") (pin "16") (pinfunction "VSS_16") (pintype "power_in"))
      (node (ref "U1") (pin "31") (pinfunction "VSSA_31") (pintype "power_in"))
      (node (ref "U1") (pin "38") (pinfunction "VSS_38") (pintype "power_in"))
      (node (ref "U1") (pin "51") (pinfunction "VSS_51") (pintype "power_in"))
      (node (ref "U1") (pin "6") (pinfunction "VBAT_6") (pintype "power_in"))
      (node (ref "U1") (pin "61") (pinfunction "VSS_61") (pintype "power_in"))
      (node (ref "U1") (pin "83") (pinfunction "VSS_83") (pintype "power_in"))
      (node (ref "U1") (pin "94") (pinfunction "VSS_94") (pintype "power_in"))
      (node (ref "U2") (pin "25") (pinfunction "NC_25") (pintype "passive"))
      (node (ref "U2") (pin "26") (pinfunction "NC_26") (pintype "passive"))
      (node (ref "U2") (pin "33") (pinfunction "GND_33") (pintype "power_in"))
      (node (ref "X1") (pin "2") (pinfunction "CASE_GND__2") (pintype "passive"))
      (node (ref "Y1") (pin "1") (pinfunction "INH_1") (pintype "passive"))
      (node (ref "Y1") (pin "2") (pinfunction "CASE_GND_2") (pintype "passive"))
    )
    (net (code "81") (name "Net-(C38-Pad1)") (class "Default")
      (node (ref "C38") (pin "1") (pinfunction "1_1") (pintype "passive"))
      (node (ref "R31") (pin "1") (pinfunction "1_1") (pintype "passive"))
      (node (ref "R32") (pin "1") (pinfunction "1_1") (pintype "passive"))
      (node (ref "R33") (pin "1") (pinfunction "1_1") (pintype "passive"))
      (node (ref "R34") (pin "1") (pinfunction "1_1") (pintype "passive"))
    )
    (net (code "82") (name "Net-(D3-A)") (class "Default")
      (node (ref "D3") (pin "2") (pinfunction "A_2") (pintype "passive"))
      (node (ref "R23") (pin "2") (pinfunction "2_2") (pintype "passive"))
    )
    (net (code "83") (name "Net-(D3-C)") (class "Default")
      (node (ref "D3") (pin "1") (pinfunction "C_1") (pintype "passive"))
      (node (ref "U2") (pin "24") (pinfunction "LED0_24") (pintype "output"))
    )
    (net (code "84") (name "Net-(D4-A)") (class "Default")
      (node (ref "D4") (pin "2") (pinfunction "A_2") (pintype "passive"))
      (node (ref "R26") (pin "2") (pinfunction "2_2") (pintype "passive"))
    )
    (net (code "85") (name "Net-(D4-C)") (class "Default")
      (node (ref "D4") (pin "1") (pinfunction "C_1") (pintype "passive"))
      (node (ref "U2") (pin "20") (pinfunction "LED1_20") (pintype "output"))
    )
    (net (code "86") (name "Net-(T1-CMT_1)") (class "Default")
      (node (ref "R31") (pin "2") (pinfunction "2_2") (pintype "passive"))
      (node (ref "T1") (pin "10") (pinfunction "CMT_1_10") (pintype "passive"))
    )
    (net (code "87") (name "Net-(T1-CMT_2)") (class "Default")
      (node (ref "R32") (pin "2") (pinfunction "2_2") (pintype "passive"))
      (node (ref "T1") (pin "15") (pinfunction "CMT_2_15") (pintype "passive"))
    )
    (net (code "88") (name "Net-(T1-RCT)") (class "Default")
      (node (ref "C37") (pin "1") (pinfunction "1_1") (pintype "passive"))
      (node (ref "T1") (pin "7") (pinfunction "RCT_7") (pintype "passive"))
    )
    (net (code "89") (name "Net-(T1-TCT)") (class "Default")
      (node (ref "C36") (pin "1") (pinfunction "1_1") (pintype "passive"))
      (node (ref "T1") (pin "2") (pinfunction "TCT_2") (pintype "passive"))
    )
    (net (code "90") (name "Net-(U1B-PH0-OSC_IN(PH0))") (class "Default")
      (node (ref "U1") (pin "23") (pinfunction "PH0-OSC_IN(PH0)_23") (pintype "bidirectional"))
      (node (ref "Y1") (pin "3") (pinfunction "OUTPUT_3") (pintype "passive"))
    )
    (net (code "91") (name "Net-(U1B-VCAP_1)") (class "Default")
      (node (ref "C30") (pin "1") (pinfunction "1_1") (pintype "passive"))
      (node (ref "U1") (pin "71") (pinfunction "VCAP_1_71") (pintype "power_in"))
    )
    (net (code "92") (name "Net-(U1B-VCAP_2)") (class "Default")
      (node (ref "C31") (pin "2") (pinfunction "2_2") (pintype "passive"))
      (node (ref "U1") (pin "106") (pinfunction "VCAP_2_106") (pintype "power_in"))
    )
    (net (code "93") (name "Net-(U2-CRS_DV)") (class "Default")
      (node (ref "R18") (pin "1") (pinfunction "1_1") (pintype "passive"))
      (node (ref "U2") (pin "13") (pinfunction "CRS_DV_13") (pintype "bidirectional"))
    )
    (net (code "94") (name "Net-(U2-REF_CLK)") (class "Default")
      (node (ref "R27") (pin "1") (pinfunction "1_1") (pintype "passive"))
      (node (ref "U2") (pin "19") (pinfunction "REF_CLK_19") (pintype "bidirectional"))
    )
    (net (code "95") (name "Net-(U2-REXT)") (class "Default")
      (node (ref "R30") (pin "2") (pinfunction "2_2") (pintype "passive"))
      (node (ref "U2") (pin "31") (pinfunction "REXT_31") (pintype "input"))
    )
    (net (code "96") (name "Net-(U2-RXD0)") (class "Default")
      (node (ref "R19") (pin "1") (pinfunction "1_1") (pintype "passive"))
      (node (ref "U2") (pin "18") (pinfunction "RXD0_18") (pintype "output"))
    )
    (net (code "97") (name "Net-(U2-RXD1)") (class "Default")
      (node (ref "R20") (pin "1") (pinfunction "1_1") (pintype "passive"))
      (node (ref "U2") (pin "17") (pinfunction "RXD1_17") (pintype "output"))
    )
    (net (code "98") (name "Net-(U2-RXER)") (class "Default")
      (node (ref "R21") (pin "1") (pinfunction "1_1") (pintype "passive"))
      (node (ref "U2") (pin "12") (pinfunction "RXER_12") (pintype "output"))
    )
    (net (code "99") (name "Net-(U2-TXD0)") (class "Default")
      (node (ref "R24") (pin "1") (pinfunction "1_1") (pintype "passive"))
      (node (ref "U2") (pin "22") (pinfunction "TXD0_22") (pintype "input"))
    )
    (net (code "100") (name "Net-(U2-TXD1)") (class "Default")
      (node (ref "R25") (pin "1") (pinfunction "1_1") (pintype "passive"))
      (node (ref "U2") (pin "23") (pinfunction "TXD1_23") (pintype "input"))
    )
    (net (code "101") (name "Net-(U2-TXEN)") (class "Default")
      (node (ref "R22") (pin "1") (pinfunction "1_1") (pintype "passive"))
      (node (ref "U2") (pin "21") (pinfunction "TXEN_21") (pintype "input"))
    )
    (net (code "102") (name "Net-(U2-XI)") (class "Default")
      (node (ref "U2") (pin "1") (pinfunction "XI_1") (pintype "passive"))
      (node (ref "X1") (pin "3") (pinfunction "OUTPUT__3") (pintype "passive"))
    )
    (net (code "103") (name "unconnected-(J2-MNT_1-Pad11)") (class "Default")
      (node (ref "J2") (pin "11") (pinfunction "MNT_1_11") (pintype "passive+no_connect"))
    )
    (net (code "104") (name "unconnected-(J2-MNT_2-Pad12)") (class "Default")
      (node (ref "J2") (pin "12") (pinfunction "MNT_2_12") (pintype "passive+no_connect"))
    )
    (net (code "105") (name "unconnected-(SWD1-Pad1)") (class "Default")
      (node (ref "SWD1") (pin "1") (pinfunction "1_1") (pintype "passive+no_connect"))
    )
    (net (code "106") (name "unconnected-(SWD1-Pad2)") (class "Default")
      (node (ref "SWD1") (pin "2") (pinfunction "2_2") (pintype "passive+no_connect"))
    )
    (net (code "107") (name "unconnected-(SWD1-Pad9)") (class "Default")
      (node (ref "SWD1") (pin "9") (pinfunction "9_9") (pintype "passive+no_connect"))
    )
    (net (code "108") (name "unconnected-(SWD1-Pad10)") (class "Default")
      (node (ref "SWD1") (pin "10") (pinfunction "10_10") (pintype "passive+no_connect"))
    )
    (net (code "109") (name "unconnected-(T1-NC_1-Pad4)") (class "Default")
      (node (ref "T1") (pin "4") (pinfunction "NC_1_4") (pintype "passive+no_connect"))
    )
    (net (code "110") (name "unconnected-(T1-NC_2-Pad5)") (class "Default")
      (node (ref "T1") (pin "5") (pinfunction "NC_2_5") (pintype "passive+no_connect"))
    )
    (net (code "111") (name "unconnected-(T1-NC_3-Pad12)") (class "Default")
      (node (ref "T1") (pin "12") (pinfunction "NC_3_12") (pintype "passive+no_connect"))
    )
    (net (code "112") (name "unconnected-(T1-NC_4-Pad13)") (class "Default")
      (node (ref "T1") (pin "13") (pinfunction "NC_4_13") (pintype "passive+no_connect"))
    )
    (net (code "113") (name "unconnected-(U1A-PA0-WKUP(PA0)-Pad34)") (class "Default")
      (node (ref "U1") (pin "34") (pinfunction "PA0-WKUP(PA0)_34") (pintype "bidirectional"))
    )
    (net (code "114") (name "unconnected-(U1A-PA3-Pad37)") (class "Default")
      (node (ref "U1") (pin "37") (pinfunction "PA3_37") (pintype "bidirectional"))
    )
    (net (code "115") (name "unconnected-(U1A-PA4-Pad40)") (class "Default")
      (node (ref "U1") (pin "40") (pinfunction "PA4_40") (pintype "bidirectional"))
    )
    (net (code "116") (name "unconnected-(U1A-PA5-Pad41)") (class "Default")
      (node (ref "U1") (pin "41") (pinfunction "PA5_41") (pintype "bidirectional"))
    )
    (net (code "117") (name "unconnected-(U1A-PA6-Pad42)") (class "Default")
      (node (ref "U1") (pin "42") (pinfunction "PA6_42") (pintype "bidirectional"))
    )
    (net (code "118") (name "unconnected-(U1A-PA12-Pad104)") (class "Default")
      (node (ref "U1") (pin "104") (pinfunction "PA12_104") (pintype "bidirectional"))
    )
    (net (code "119") (name "unconnected-(U1A-PB0-Pad46)") (class "Default")
      (node (ref "U1") (pin "46") (pinfunction "PB0_46") (pintype "bidirectional"))
    )
    (net (code "120") (name "unconnected-(U1A-PB1-Pad47)") (class "Default")
      (node (ref "U1") (pin "47") (pinfunction "PB1_47") (pintype "bidirectional"))
    )
    (net (code "121") (name "unconnected-(U1A-PC0-Pad26)") (class "Default")
      (node (ref "U1") (pin "26") (pinfunction "PC0_26") (pintype "bidirectional"))
    )
    (net (code "122") (name "unconnected-(U1A-PC6-Pad96)") (class "Default")
      (node (ref "U1") (pin "96") (pinfunction "PC6_96") (pintype "bidirectional"))
    )
    (net (code "123") (name "unconnected-(U1A-PC7-Pad97)") (class "Default")
      (node (ref "U1") (pin "97") (pinfunction "PC7_97") (pintype "bidirectional"))
    )
    (net (code "124") (name "unconnected-(U1A-PC13-Pad7)") (class "Default")
      (node (ref "U1") (pin "7") (pinfunction "PC13_7") (pintype "bidirectional"))
    )
    (net (code "125") (name "unconnected-(U1A-PC14-OSC32_IN(PC14)-Pad8)") (class "Default")
      (node (ref "U1") (pin "8") (pinfunction "PC14-OSC32_IN(PC14)_8") (pintype "bidirectional"))
    )
    (net (code "126") (name "unconnected-(U1A-PC15-OSC32_OUT(PC15)-Pad9)") (class "Default")
      (node (ref "U1") (pin "9") (pinfunction "PC15-OSC32_OUT(PC15)_9") (pintype "bidirectional"))
    )
    (net (code "127") (name "unconnected-(U1A-PD2-Pad116)") (class "Default")
      (node (ref "U1") (pin "116") (pinfunction "PD2_116") (pintype "bidirectional"))
    )
    (net (code "128") (name "unconnected-(U1A-PD3-Pad117)") (class "Default")
      (node (ref "U1") (pin "117") (pinfunction "PD3_117") (pintype "bidirectional"))
    )
    (net (code "129") (name "unconnected-(U1A-PD4-Pad118)") (class "Default")
      (node (ref "U1") (pin "118") (pinfunction "PD4_118") (pintype "bidirectional"))
    )
    (net (code "130") (name "unconnected-(U1A-PD5-Pad119)") (class "Default")
      (node (ref "U1") (pin "119") (pinfunction "PD5_119") (pintype "bidirectional"))
    )
    (net (code "131") (name "unconnected-(U1A-PD6-Pad122)") (class "Default")
      (node (ref "U1") (pin "122") (pinfunction "PD6_122") (pintype "bidirectional"))
    )
    (net (code "132") (name "unconnected-(U1A-PD7-Pad123)") (class "Default")
      (node (ref "U1") (pin "123") (pinfunction "PD7_123") (pintype "bidirectional"))
    )
    (net (code "133") (name "unconnected-(U1A-PD8-Pad77)") (class "Default")
      (node (ref "U1") (pin "77") (pinfunction "PD8_77") (pintype "bidirectional"))
    )
    (net (code "134") (name "unconnected-(U1A-PD9-Pad78)") (class "Default")
      (node (ref "U1") (pin "78") (pinfunction "PD9_78") (pintype "bidirectional"))
    )
    (net (code "135") (name "unconnected-(U1A-PD13-Pad82)") (class "Default")
      (node (ref "U1") (pin "82") (pinfunction "PD13_82") (pintype "bidirectional"))
    )
    (net (code "136") (name "unconnected-(U1A-PD14-Pad85)") (class "Default")
      (node (ref "U1") (pin "85") (pinfunction "PD14_85") (pintype "bidirectional"))
    )
    (net (code "137") (name "unconnected-(U1B-PDR_ON-Pad143)") (class "Default")
      (node (ref "U1") (pin "143") (pinfunction "PDR_ON_143") (pintype "input+no_connect"))
    )
    (net (code "138") (name "unconnected-(U1B-PE6-Pad5)") (class "Default")
      (node (ref "U1") (pin "5") (pinfunction "PE6_5") (pintype "bidirectional"))
    )
    (net (code "139") (name "unconnected-(U1B-PF2-Pad12)") (class "Default")
      (node (ref "U1") (pin "12") (pinfunction "PF2_12") (pintype "bidirectional"))
    )
    (net (code "140") (name "unconnected-(U1B-PF3-Pad13)") (class "Default")
      (node (ref "U1") (pin "13") (pinfunction "PF3_13") (pintype "bidirectional"))
    )
    (net (code "141") (name "unconnected-(U1B-PF4-Pad14)") (class "Default")
      (node (ref "U1") (pin "14") (pinfunction "PF4_14") (pintype "bidirectional"))
    )
    (net (code "142") (name "unconnected-(U1B-PF5-Pad15)") (class "Default")
      (node (ref "U1") (pin "15") (pinfunction "PF5_15") (pintype "bidirectional"))
    )
    (net (code "143") (name "unconnected-(U1B-PF6-Pad18)") (class "Default")
      (node (ref "U1") (pin "18") (pinfunction "PF6_18") (pintype "bidirectional"))
    )
    (net (code "144") (name "unconnected-(U1B-PF7-Pad19)") (class "Default")
      (node (ref "U1") (pin "19") (pinfunction "PF7_19") (pintype "bidirectional"))
    )
    (net (code "145") (name "unconnected-(U1B-PF8-Pad20)") (class "Default")
      (node (ref "U1") (pin "20") (pinfunction "PF8_20") (pintype "bidirectional"))
    )
    (net (code "146") (name "unconnected-(U1B-PF9-Pad21)") (class "Default")
      (node (ref "U1") (pin "21") (pinfunction "PF9_21") (pintype "bidirectional"))
    )
    (net (code "147") (name "unconnected-(U1B-PF10-Pad22)") (class "Default")
      (node (ref "U1") (pin "22") (pinfunction "PF10_22") (pintype "bidirectional"))
    )
    (net (code "148") (name "unconnected-(U1B-PF11-Pad49)") (class "Default")
      (node (ref "U1") (pin "49") (pinfunction "PF11_49") (pintype "bidirectional"))
    )
    (net (code "149") (name "unconnected-(U1B-PF12-Pad50)") (class "Default")
      (node (ref "U1") (pin "50") (pinfunction "PF12_50") (pintype "bidirectional"))
    )
    (net (code "150") (name "unconnected-(U1B-PF13-Pad53)") (class "Default")
      (node (ref "U1") (pin "53") (pinfunction "PF13_53") (pintype "bidirectional"))
    )
    (net (code "151") (name "unconnected-(U1B-PF14-Pad54)") (class "Default")
      (node (ref "U1") (pin "54") (pinfunction "PF14_54") (pintype "bidirectional"))
    )
    (net (code "152") (name "unconnected-(U1B-PF15-Pad55)") (class "Default")
      (node (ref "U1") (pin "55") (pinfunction "PF15_55") (pintype "bidirectional"))
    )
    (net (code "153") (name "unconnected-(U1B-PG0-Pad56)") (class "Default")
      (node (ref "U1") (pin "56") (pinfunction "PG0_56") (pintype "bidirectional"))
    )
    (net (code "154") (name "unconnected-(U1B-PG1-Pad57)") (class "Default")
      (node (ref "U1") (pin "57") (pinfunction "PG1_57") (pintype "bidirectional"))
    )
    (net (code "155") (name "unconnected-(U1B-PG2-Pad87)") (class "Default")
      (node (ref "U1") (pin "87") (pinfunction "PG2_87") (pintype "bidirectional"))
    )
    (net (code "156") (name "unconnected-(U1B-PG3-Pad88)") (class "Default")
      (node (ref "U1") (pin "88") (pinfunction "PG3_88") (pintype "bidirectional"))
    )
    (net (code "157") (name "unconnected-(U1B-PG4-Pad89)") (class "Default")
      (node (ref "U1") (pin "89") (pinfunction "PG4_89") (pintype "bidirectional"))
    )
    (net (code "158") (name "unconnected-(U1B-PG5-Pad90)") (class "Default")
      (node (ref "U1") (pin "90") (pinfunction "PG5_90") (pintype "bidirectional"))
    )
    (net (code "159") (name "unconnected-(U1B-PG6-Pad91)") (class "Default")
      (node (ref "U1") (pin "91") (pinfunction "PG6_91") (pintype "bidirectional"))
    )
    (net (code "160") (name "unconnected-(U1B-PG7-Pad92)") (class "Default")
      (node (ref "U1") (pin "92") (pinfunction "PG7_92") (pintype "bidirectional"))
    )
    (net (code "161") (name "unconnected-(U1B-PG8-Pad93)") (class "Default")
      (node (ref "U1") (pin "93") (pinfunction "PG8_93") (pintype "bidirectional"))
    )
    (net (code "162") (name "unconnected-(U1B-PG9-Pad124)") (class "Default")
      (node (ref "U1") (pin "124") (pinfunction "PG9_124") (pintype "bidirectional"))
    )
    (net (code "163") (name "unconnected-(U1B-PG10-Pad125)") (class "Default")
      (node (ref "U1") (pin "125") (pinfunction "PG10_125") (pintype "bidirectional"))
    )
    (net (code "164") (name "unconnected-(U1B-PG11-Pad126)") (class "Default")
      (node (ref "U1") (pin "126") (pinfunction "PG11_126") (pintype "bidirectional"))
    )
    (net (code "165") (name "unconnected-(U1B-PG12-Pad127)") (class "Default")
      (node (ref "U1") (pin "127") (pinfunction "PG12_127") (pintype "bidirectional"))
    )
    (net (code "166") (name "unconnected-(U1B-PG13-Pad128)") (class "Default")
      (node (ref "U1") (pin "128") (pinfunction "PG13_128") (pintype "bidirectional"))
    )
    (net (code "167") (name "unconnected-(U1B-PG14-Pad129)") (class "Default")
      (node (ref "U1") (pin "129") (pinfunction "PG14_129") (pintype "bidirectional"))
    )
    (net (code "168") (name "unconnected-(U1B-PH1-OSC_OUT(PH1)-Pad24)") (class "Default")
      (node (ref "U1") (pin "24") (pinfunction "PH1-OSC_OUT(PH1)_24") (pintype "bidirectional+no_connect"))
    )
    (net (code "169") (name "unconnected-(U2-CONFIG1-Pad27)") (class "Default")
      (node (ref "U2") (pin "27") (pinfunction "CONFIG1_27") (pintype "bidirectional+no_connect"))
    )
    (net (code "170") (name "unconnected-(U2-PHYAD0-Pad14)") (class "Default")
      (node (ref "U2") (pin "14") (pinfunction "PHYAD0_14") (pintype "bidirectional+no_connect"))
    )
    (net (code "171") (name "unconnected-(U2-PHYAD1-Pad16)") (class "Default")
      (node (ref "U2") (pin "16") (pinfunction "PHYAD1_16") (pintype "bidirectional+no_connect"))
    )
    (net (code "172") (name "unconnected-(U2-XO-Pad2)") (class "Default")
      (node (ref "U2") (pin "2") (pinfunction "XO_2") (pintype "passive+no_connect"))
    )
  )
)
